# Cpu.net
KiCad netlist of a schematic drawn in Altium Designer
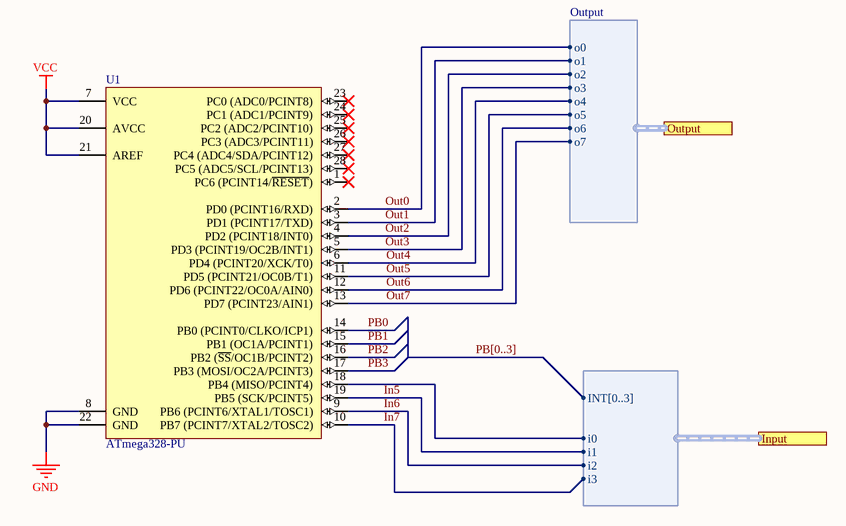
[diagram p0: Cpu.SchDoc]

(export (version "E")
  (design (tool "Eeschema 10.0.6"))
  (components
    (comp (ref "U1")
      (value "ATmega328-PU")
      (footprint "28P3")
      (libsource (lib "Altium Content Vault") (part "MC-8B-ATM48-IL28"))
    )
  )
  (nets
    (net (code "3") (name "/In5") (class "Default")
      (node (ref "U1") (pin "19") (pinfunction "PB5_(SCK/PCINT5)_19") (pintype "bidirectional"))
    )
    (net (code "4") (name "/In6") (class "Default")
      (node (ref "U1") (pin "9") (pinfunction "PB6_(PCINT6/XTAL1/TOSC1)_9") (pintype "bidirectional"))
    )
    (net (code "5") (name "/In7") (class "Default")
      (node (ref "U1") (pin "10") (pinfunction "PB7_(PCINT7/XTAL2/TOSC2)_10") (pintype "bidirectional"))
    )
    (net (code "7") (name "/Out0") (class "Default")
      (node (ref "U1") (pin "2") (pinfunction "PD0_(PCINT16/RXD)_2") (pintype "bidirectional"))
    )
    (net (code "8") (name "/Out1") (class "Default")
      (node (ref "U1") (pin "3") (pinfunction "PD1_(PCINT17/TXD)_3") (pintype "bidirectional"))
    )
    (net (code "9") (name "/Out2") (class "Default")
      (node (ref "U1") (pin "4") (pinfunction "PD2_(PCINT18/INT0)_4") (pintype "bidirectional"))
    )
    (net (code "10") (name "/Out3") (class "Default")
      (node (ref "U1") (pin "5") (pinfunction "PD3_(PCINT19/OC2B/INT1)_5") (pintype "bidirectional"))
    )
    (net (code "11") (name "/Out4") (class "Default")
      (node (ref "U1") (pin "6") (pinfunction "PD4_(PCINT20/XCK/T0)_6") (pintype "bidirectional"))
    )
    (net (code "12") (name "/Out5") (class "Default")
      (node (ref "U1") (pin "11") (pinfunction "PD5_(PCINT21/OC0B/T1)_11") (pintype "bidirectional"))
    )
    (net (code "13") (name "/Out6") (class "Default")
      (node (ref "U1") (pin "12") (pinfunction "PD6_(PCINT22/OC0A/AIN0)_12") (pintype "bidirectional"))
    )
    (net (code "14") (name "/Out7") (class "Default")
      (node (ref "U1") (pin "13") (pinfunction "PD7_(PCINT23/AIN1)_13") (pintype "bidirectional"))
    )
    (net (code "15") (name "/PB0") (class "Default")
      (node (ref "U1") (pin "14") (pinfunction "PB0_(PCINT0/CLKO/ICP1)_14") (pintype "bidirectional"))
    )
    (net (code "16") (name "/PB1") (class "Default")
      (node (ref "U1") (pin "15") (pinfunction "PB1_(OC1A/PCINT1)_15") (pintype "bidirectional"))
    )
    (net (code "17") (name "/PB2") (class "Default")
      (node (ref "U1") (pin "16") (pinfunction "PB2_(~{SS}/OC1B/PCINT2)_16") (pintype "bidirectional"))
    )
    (net (code "18") (name "/PB3") (class "Default")
      (node (ref "U1") (pin "17") (pinfunction "PB3_(MOSI/OC2A/PCINT3)_17") (pintype "bidirectional"))
    )
    (net (code "19") (name "/i0") (class "Default")
      (node (ref "U1") (pin "18") (pinfunction "PB4_(MISO/PCINT4)_18") (pintype "bidirectional"))
    )
    (net (code "22") (name "GND") (class "Default")
      (node (ref "U1") (pin "22") (pinfunction "GND_22") (pintype "power_in"))
      (node (ref "U1") (pin "8") (pinfunction "GND_8") (pintype "power_in"))
    )
    (net (code "23") (name "VCC") (class "Default")
      (node (ref "U1") (pin "20") (pinfunction "AVCC_20") (pintype "power_in"))
      (node (ref "U1") (pin "21") (pinfunction "AREF_21") (pintype "power_in"))
      (node (ref "U1") (pin "7") (pinfunction "VCC_7") (pintype "power_in"))
    )
    (net (code "24") (name "unconnected-(U1-PC0_(ADC0{slash}PCINT8)-Pad23)") (class "Default")
      (node (ref "U1") (pin "23") (pinfunction "PC0_(ADC0/PCINT8)_23") (pintype "bidirectional+no_connect"))
    )
    (net (code "25") (name "unconnected-(U1-PC1_(ADC1{slash}PCINT9)-Pad24)") (class "Default")
      (node (ref "U1") (pin "24") (pinfunction "PC1_(ADC1/PCINT9)_24") (pintype "bidirectional+no_connect"))
    )
    (net (code "26") (name "unconnected-(U1-PC2_(ADC2{slash}PCINT10)-Pad25)") (class "Default")
      (node (ref "U1") (pin "25") (pinfunction "PC2_(ADC2/PCINT10)_25") (pintype "bidirectional+no_connect"))
    )
    (net (code "27") (name "unconnected-(U1-PC3_(ADC3{slash}PCINT11)-Pad26)") (class "Default")
      (node (ref "U1") (pin "26") (pinfunction "PC3_(ADC3/PCINT11)_26") (pintype "bidirectional+no_connect"))
    )
    (net (code "28") (name "unconnected-(U1-PC4_(ADC4{slash}SDA{slash}PCINT12)-Pad27)") (class "Default")
      (node (ref "U1") (pin "27") (pinfunction "PC4_(ADC4/SDA/PCINT12)_27") (pintype "bidirectional+no_connect"))
    )
    (net (code "29") (name "unconnected-(U1-PC5_(ADC5{slash}SCL{slash}PCINT13)-Pad28)") (class "Default")
      (node (ref "U1") (pin "28") (pinfunction "PC5_(ADC5/SCL/PCINT13)_28") (pintype "bidirectional+no_connect"))
    )
    (net (code "30") (name "unconnected-(U1-PC6_(PCINT14{slash}~{RESET})-Pad1)") (class "Default")
      (node (ref "U1") (pin "1") (pinfunction "PC6_(PCINT14/~{RESET})_1") (pintype "bidirectional+no_connect"))
    )
  )
)
